# esp-06_breakout.net
KiCad netlist of a schematic drawn in EAGLE
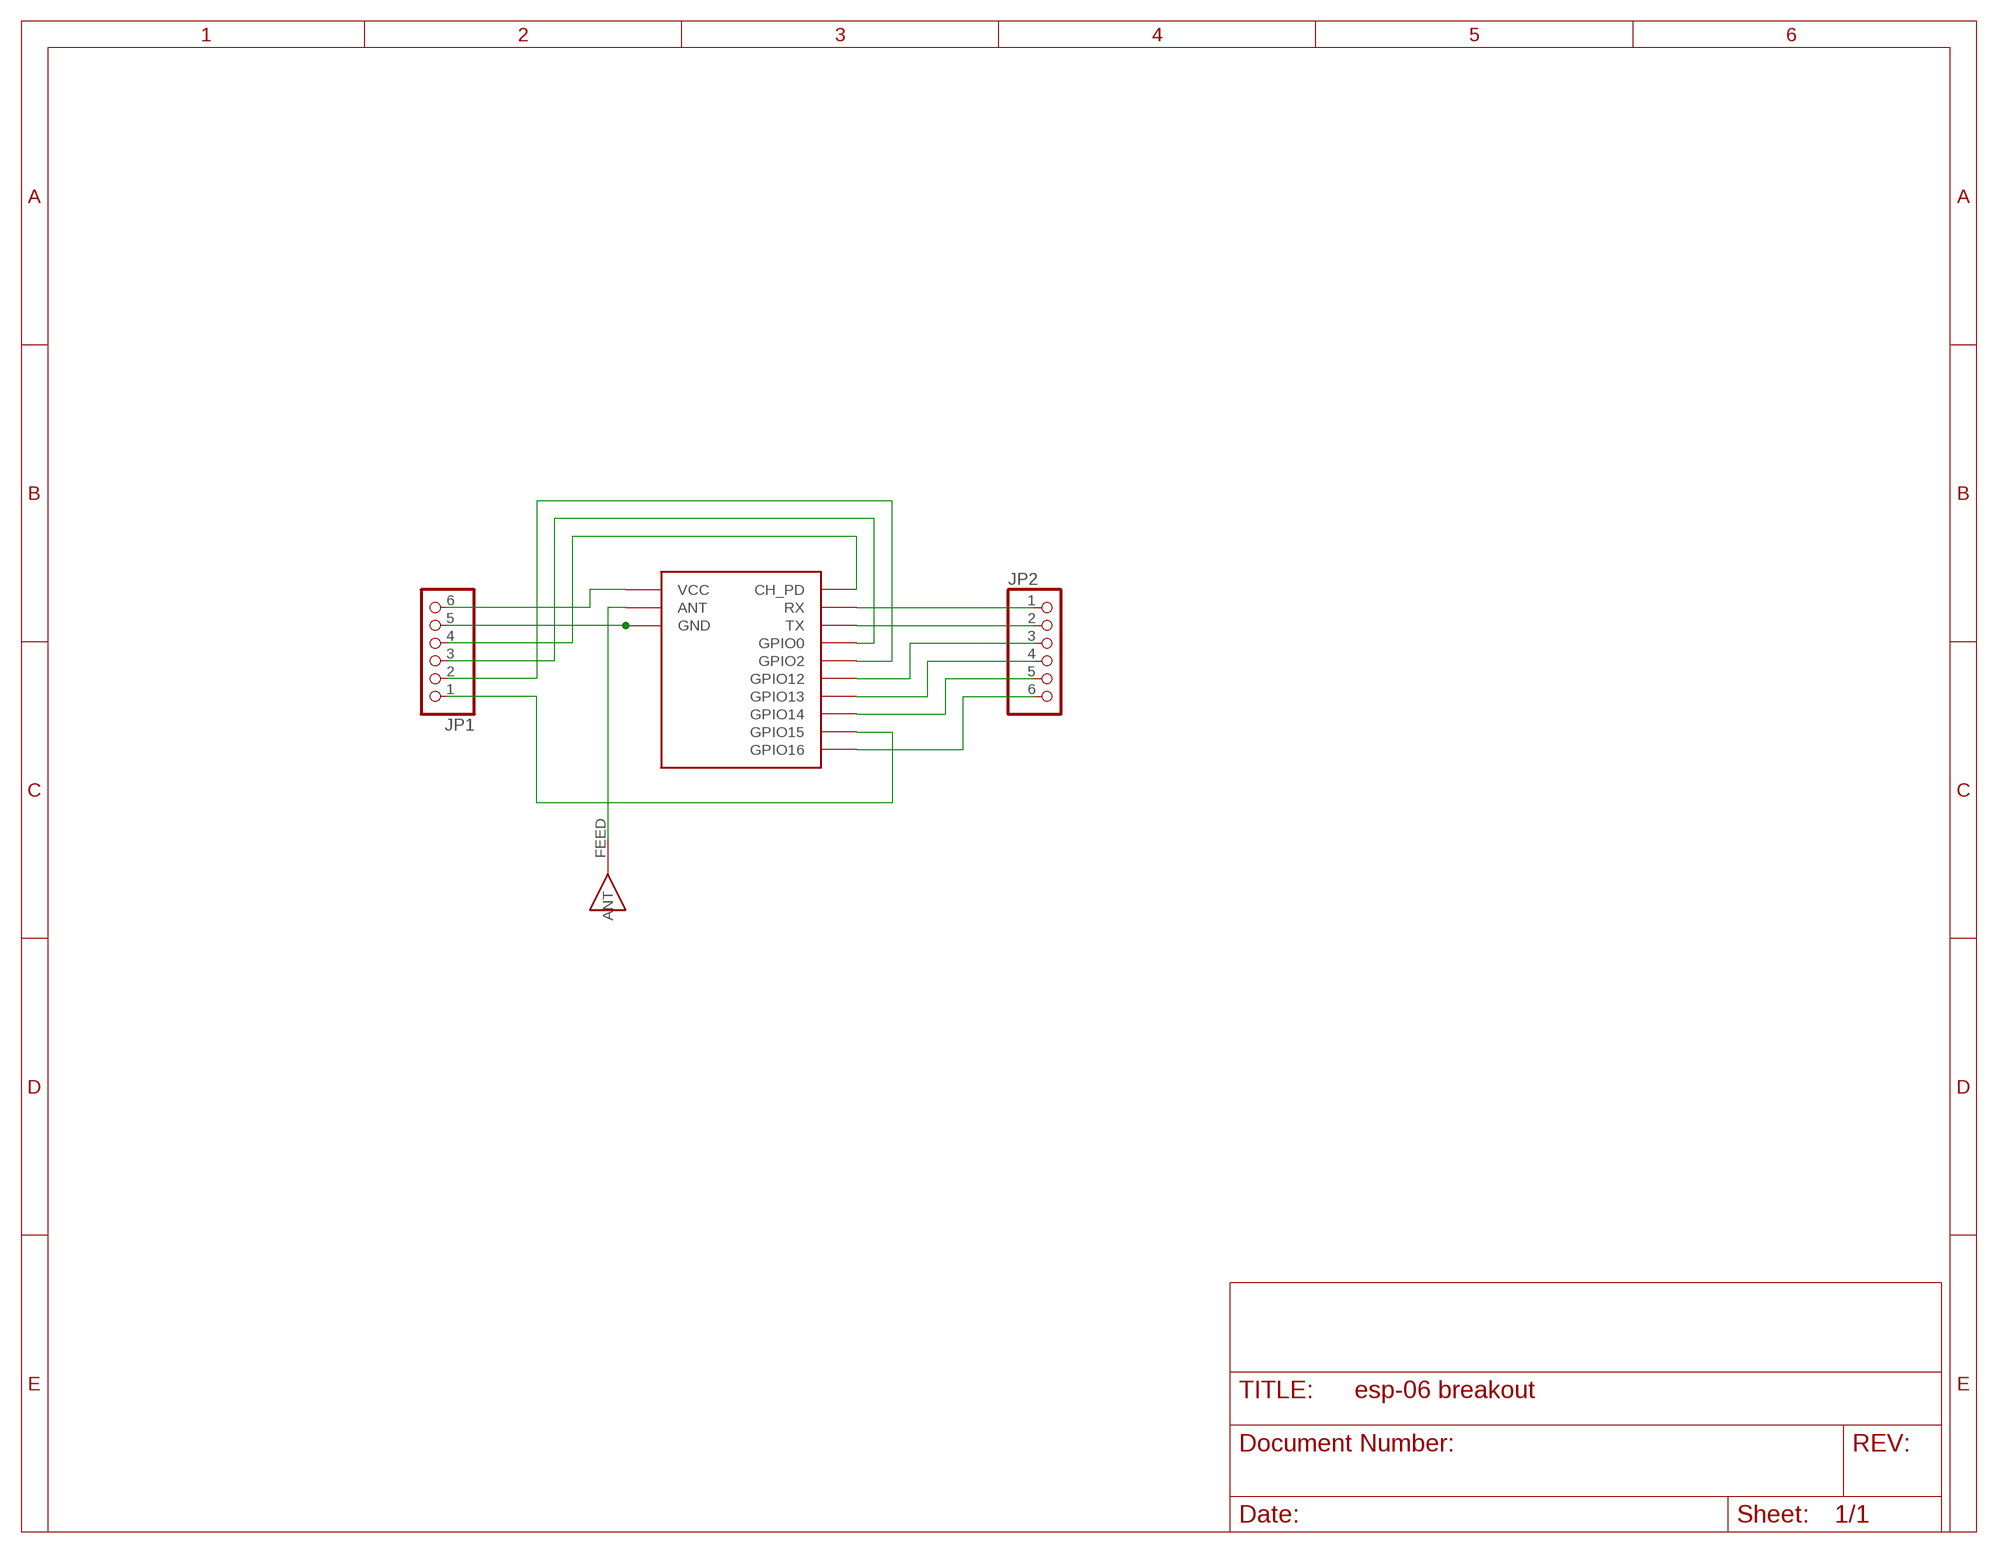
[diagram p0: schematic, sheet 1]

(export (version "E")
  (design (tool "Eeschema 10.0.6"))
  (components
    (comp (ref "JP1")
      (value "PINHD-1X6")
      (footprint "eagle-import:1X06")
      (libsource (lib "eagle-import") (part "PINHD-1X6"))
    )
    (comp (ref "JP2")
      (value "PINHD-1X6")
      (footprint "eagle-import:1X06")
      (libsource (lib "eagle-import") (part "PINHD-1X6"))
    )
    (comp (ref "U$1")
      (value "ESP06")
      (footprint "eagle-import:ESP06")
      (libsource (lib "eagle-import") (part "ESP06"))
    )
    (comp (ref "U$2")
      (value "ANT")
      (footprint "eagle-import:ANTENNA-CERAMIC")
      (libsource (lib "eagle-import") (part "ANT"))
    )
  )
  (nets
    (net (code "1") (name "Net-(JP1-Pad1)") (class "Default")
      (node (ref "JP1") (pin "1") (pinfunction "1_1") (pintype "passive"))
      (node (ref "U$1") (pin "GPIO15") (pinfunction "GPIO15_GPIO15") (pintype "bidirectional"))
    )
    (net (code "2") (name "Net-(JP1-Pad2)") (class "Default")
      (node (ref "JP1") (pin "2") (pinfunction "2_2") (pintype "passive"))
      (node (ref "U$1") (pin "GPIO2") (pinfunction "GPIO2_GPIO2") (pintype "bidirectional"))
    )
    (net (code "3") (name "Net-(JP1-Pad3)") (class "Default")
      (node (ref "JP1") (pin "3") (pinfunction "3_3") (pintype "passive"))
      (node (ref "U$1") (pin "GPIO0") (pinfunction "GPIO0_GPIO0") (pintype "bidirectional"))
    )
    (net (code "4") (name "Net-(JP1-Pad4)") (class "Default")
      (node (ref "JP1") (pin "4") (pinfunction "4_4") (pintype "passive"))
      (node (ref "U$1") (pin "CH_PD") (pinfunction "CH_PD_CH_PD") (pintype "bidirectional"))
    )
    (net (code "5") (name "Net-(JP1-Pad6)") (class "Default")
      (node (ref "JP1") (pin "6") (pinfunction "6_6") (pintype "passive"))
      (node (ref "U$1") (pin "VCC") (pinfunction "VCC_VCC") (pintype "bidirectional"))
    )
    (net (code "6") (name "Net-(JP2-Pad1)") (class "Default")
      (node (ref "JP2") (pin "1") (pinfunction "1_1") (pintype "passive"))
      (node (ref "U$1") (pin "RX") (pinfunction "RX_RX") (pintype "bidirectional"))
    )
    (net (code "7") (name "Net-(JP2-Pad2)") (class "Default")
      (node (ref "JP2") (pin "2") (pinfunction "2_2") (pintype "passive"))
      (node (ref "U$1") (pin "TX") (pinfunction "TX_TX") (pintype "bidirectional"))
    )
    (net (code "8") (name "Net-(JP2-Pad3)") (class "Default")
      (node (ref "JP2") (pin "3") (pinfunction "3_3") (pintype "passive"))
      (node (ref "U$1") (pin "GPIO12") (pinfunction "GPIO12_GPIO12") (pintype "bidirectional"))
    )
    (net (code "9") (name "Net-(JP2-Pad4)") (class "Default")
      (node (ref "JP2") (pin "4") (pinfunction "4_4") (pintype "passive"))
      (node (ref "U$1") (pin "GPIO13") (pinfunction "GPIO13_GPIO13") (pintype "bidirectional"))
    )
    (net (code "10") (name "Net-(JP2-Pad5)") (class "Default")
      (node (ref "JP2") (pin "5") (pinfunction "5_5") (pintype "passive"))
      (node (ref "U$1") (pin "GPIO14") (pinfunction "GPIO14_GPIO14") (pintype "bidirectional"))
    )
    (net (code "11") (name "Net-(JP2-Pad6)") (class "Default")
      (node (ref "JP2") (pin "6") (pinfunction "6_6") (pintype "passive"))
      (node (ref "U$1") (pin "GPIO16") (pinfunction "GPIO16_GPIO16") (pintype "bidirectional"))
    )
    (net (code "12") (name "Net-(U$1-GND2)") (class "Default")
      (node (ref "JP1") (pin "5") (pinfunction "5_5") (pintype "passive"))
      (node (ref "U$1") (pin "GND") (pinfunction "GND_GND") (pintype "bidirectional"))
      (node (ref "U$1") (pin "GND1") (pinfunction "GND2_GND1") (pintype "bidirectional"))
      (node (ref "U$1") (pin "GND2") (pinfunction "GND3_GND2") (pintype "bidirectional"))
      (node (ref "U$1") (pin "GND3") (pinfunction "GND4_GND3") (pintype "bidirectional"))
      (node (ref "U$1") (pin "GND4") (pinfunction "GND5_GND4") (pintype "bidirectional"))
      (node (ref "U$1") (pin "GND5") (pinfunction "GND6_GND5") (pintype "bidirectional"))
      (node (ref "U$1") (pin "GND6") (pinfunction "GND7_GND6") (pintype "bidirectional"))
      (node (ref "U$1") (pin "GND7") (pinfunction "GND8_GND7") (pintype "bidirectional"))
    )
    (net (code "13") (name "Net-(U$2-ANT)") (class "Default")
      (node (ref "U$1") (pin "ANT") (pinfunction "ANT_ANT") (pintype "bidirectional"))
      (node (ref "U$2") (pin "FEED") (pinfunction "ANT_FEED") (pintype "bidirectional"))
    )
  )
)
